# 03_-_ESP32.net
KiCad netlist of a schematic drawn in Altium Designer
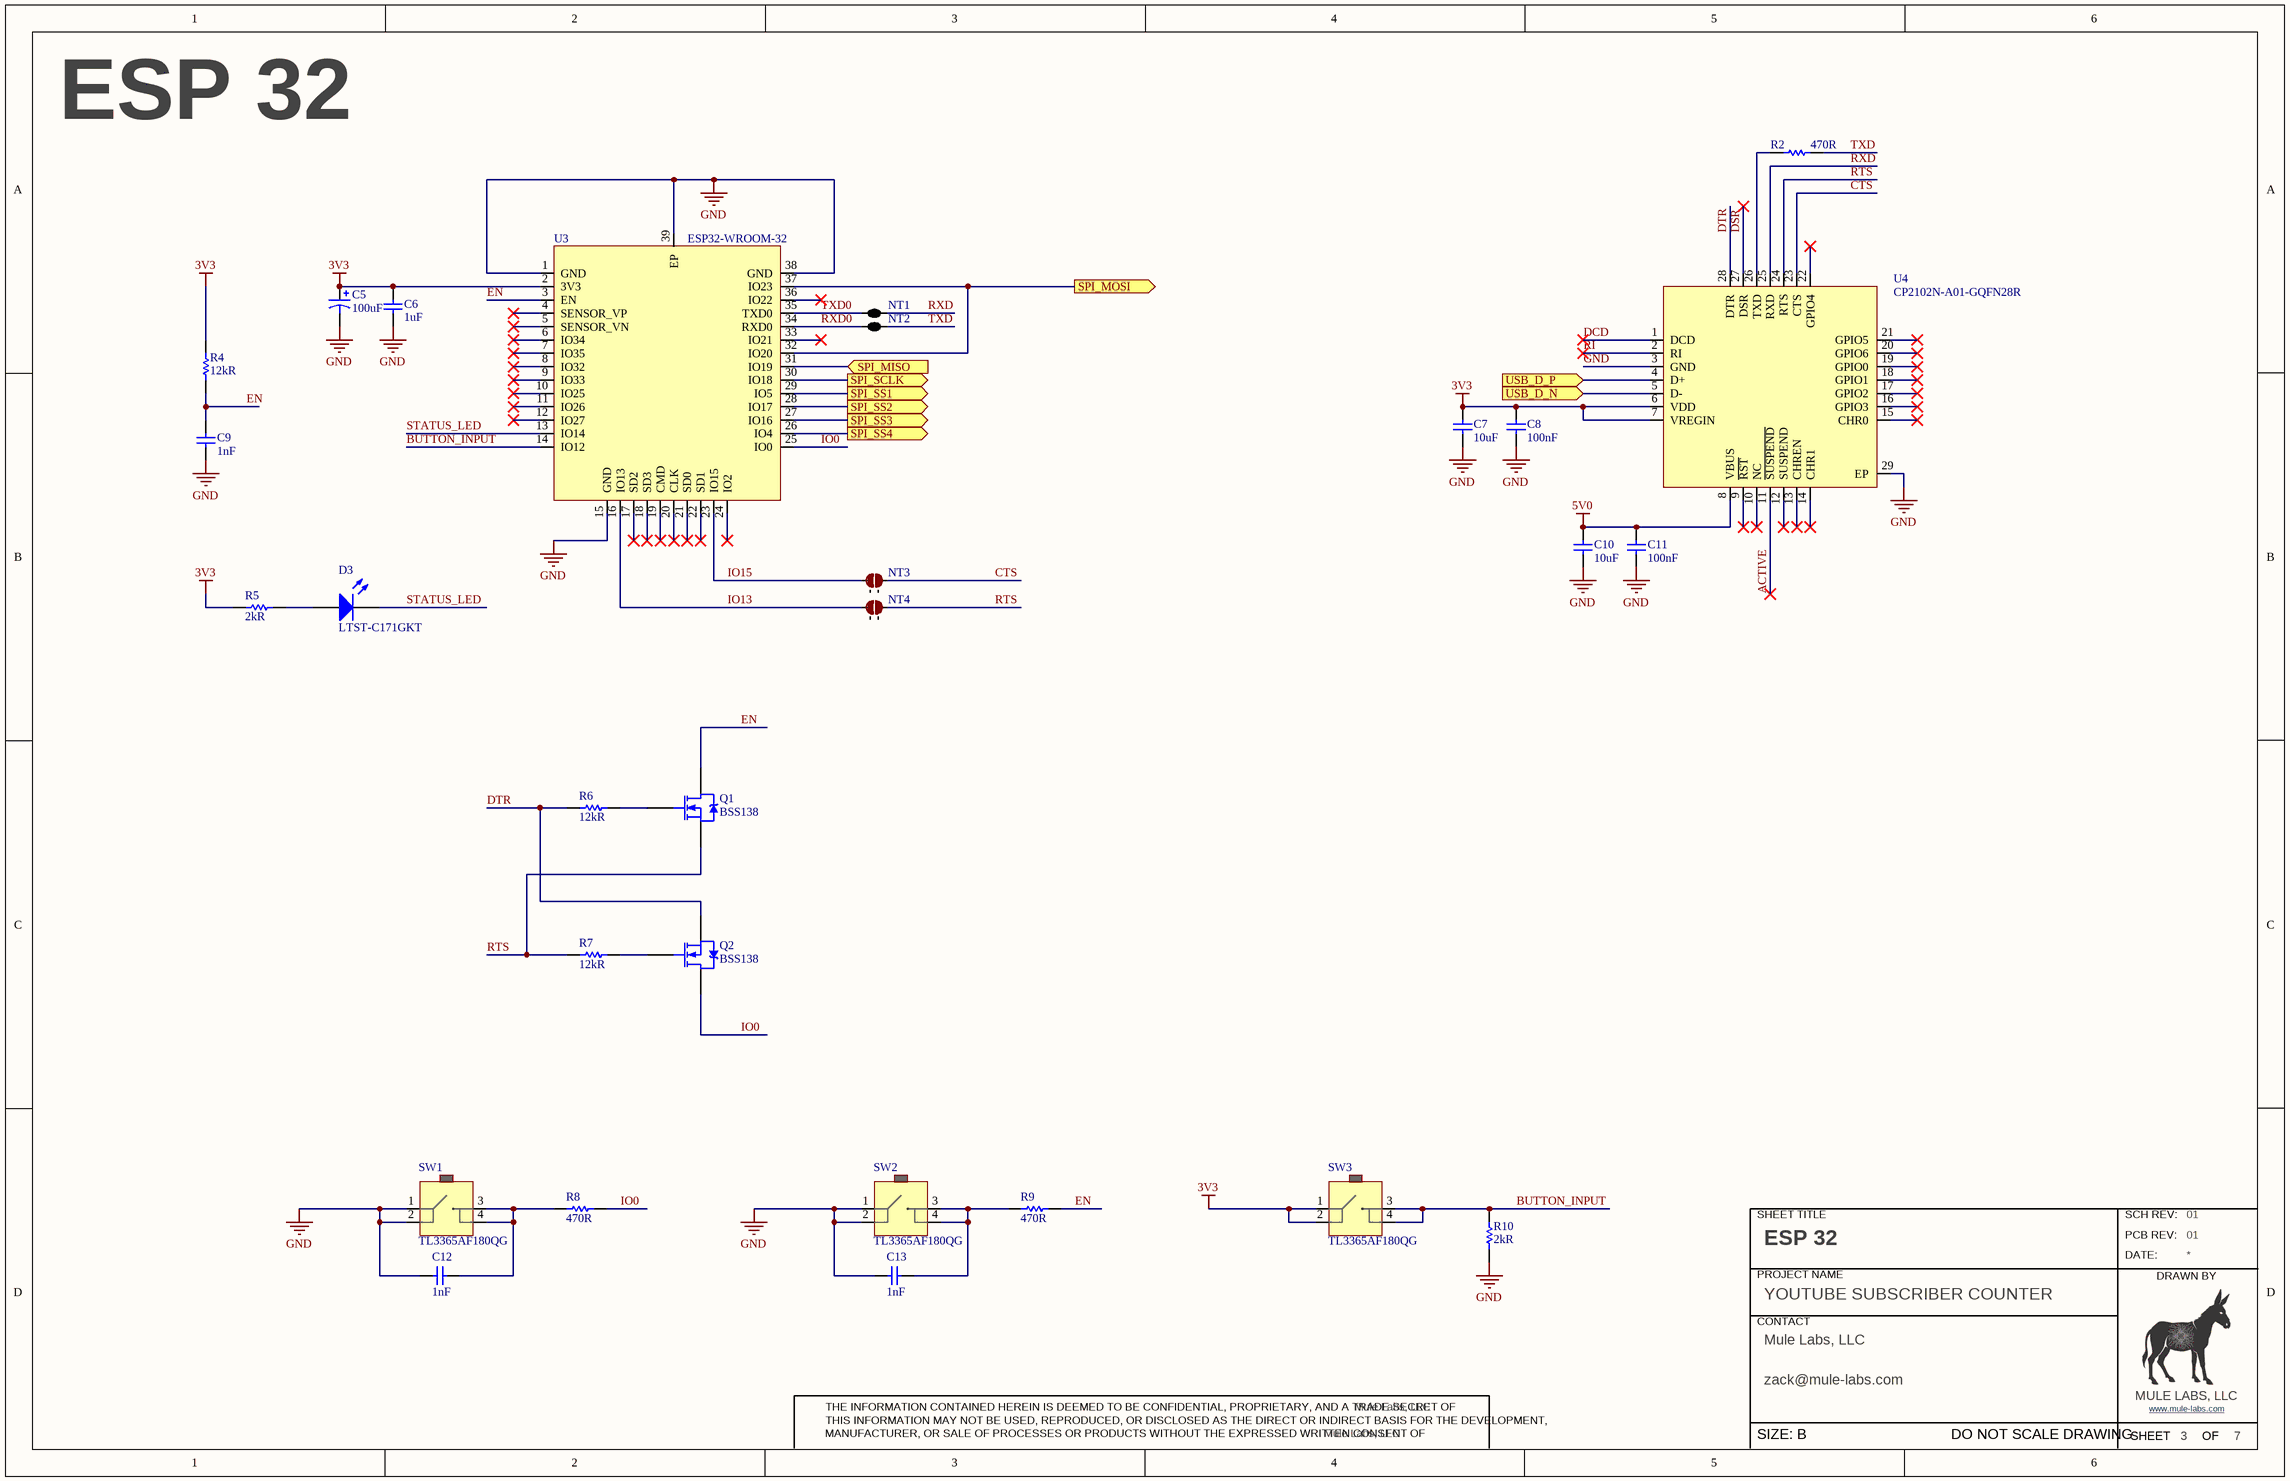
[diagram p0: [03] - ESP32.SchDoc]

(export (version "E")
  (design (tool "Eeschema 10.0.6"))
  (components
    (comp (ref "C5")
      (value "100uF")
      (footprint "INCH 0603 - METRIC 1608 - H090")
      (description "CAP TANT 100UF 20% 6.3V 0603")
      (fields
        (field (name "MANUFACTURER") "Kyocera AVX")
        (field (name "MANUFACTURER PART NUMBER") "F980J107MMAAXE")
      )
      (libsource (lib "Capacitors") (part "F980J107MMAAXE"))
    )
    (comp (ref "C6")
      (value "1uF")
      (footprint "INCH 0603 - METRIC 1608 - H090")
      (description "CAP CER 1UF 16V X7R 0603")
      (fields
        (field (name "MANUFACTURER") "Samsung")
        (field (name "MANUFACTURER PART NUMBER") "CL10B105KO8NNNC")
      )
      (libsource (lib "Capacitors") (part "CL10B105KO8NNNC"))
    )
    (comp (ref "C7")
      (value "10uF")
      (footprint "INCH 0603 - METRIC 1608 - H090")
      (description "CAP CER 10UF 10V X5R 0603")
      (fields
        (field (name "MANUFACTURER") "Murata")
        (field (name "MANUFACTURER PART NUMBER") "GRM188R61A106ME69D")
      )
      (libsource (lib "Capacitors") (part "GRM188R61A106ME69D"))
    )
    (comp (ref "C8")
      (value "100nF")
      (footprint "INCH 0603 - METRIC 1608 - H090")
      (description "CAP CER 0.1UF 25V X7R 0603")
      (fields
        (field (name "MANUFACTURER") "TDK")
        (field (name "MANUFACTURER PART NUMBER") "CGA3E2X7R1E104K080AA")
      )
      (libsource (lib "Capacitors") (part "CGA3E2X7R1E104K080AA"))
    )
    (comp (ref "C9")
      (value "1nF")
      (footprint "INCH 0603 - METRIC 1608 - H090")
      (description "CAP CER 1000PF 50V C0G/NP0 0603")
      (fields
        (field (name "MANUFACTURER") "Samsung")
        (field (name "MANUFACTURER PART NUMBER") "CL10C102JB8NNNC")
      )
      (libsource (lib "Capacitors") (part "CL10C102JB8NNNC"))
    )
    (comp (ref "C10")
      (value "10uF")
      (footprint "INCH 0603 - METRIC 1608 - H090")
      (description "CAP CER 10UF 10V X5R 0603")
      (fields
        (field (name "MANUFACTURER") "Murata")
        (field (name "MANUFACTURER PART NUMBER") "GRM188R61A106ME69D")
      )
      (libsource (lib "Capacitors") (part "GRM188R61A106ME69D"))
    )
    (comp (ref "C11")
      (value "100nF")
      (footprint "INCH 0603 - METRIC 1608 - H090")
      (description "CAP CER 0.1UF 25V X7R 0603")
      (fields
        (field (name "MANUFACTURER") "TDK")
        (field (name "MANUFACTURER PART NUMBER") "CGA3E2X7R1E104K080AA")
      )
      (libsource (lib "Capacitors") (part "CGA3E2X7R1E104K080AA"))
    )
    (comp (ref "C12")
      (value "1nF")
      (footprint "INCH 0603 - METRIC 1608 - H090")
      (description "CAP CER 1000PF 50V C0G/NP0 0603")
      (fields
        (field (name "MANUFACTURER") "Samsung")
        (field (name "MANUFACTURER PART NUMBER") "CL10C102JB8NNNC")
      )
      (libsource (lib "Capacitors") (part "CL10C102JB8NNNC"))
    )
    (comp (ref "C13")
      (value "1nF")
      (footprint "INCH 0603 - METRIC 1608 - H090")
      (description "CAP CER 1000PF 50V C0G/NP0 0603")
      (fields
        (field (name "MANUFACTURER") "Samsung")
        (field (name "MANUFACTURER PART NUMBER") "CL10C102JB8NNNC")
      )
      (libsource (lib "Capacitors") (part "CL10C102JB8NNNC"))
    )
    (comp (ref "D3")
      (value "LTST-C171GKT")
      (footprint "LED - 0805 - GREEN")
      (fields (field (name "MANUFACTURER") "Vishay Lite-On"))
      (libsource (lib "LEDs") (part "LTST-C171GKT"))
    )
    (comp (ref "NT1")
      (value "2 way net tie junction")
      (footprint "2way_HP")
      (libsource (lib "Net Ties") (part "2way"))
    )
    (comp (ref "NT2")
      (value "2 way net tie junction")
      (footprint "2way_HP")
      (libsource (lib "Net Ties") (part "2way"))
    )
    (comp (ref "NT3")
      (value "2 way net solder junction - Normally Open")
      (footprint "2waySolder_NO")
      (libsource (lib "Net Ties") (part "2waySolderNO"))
    )
    (comp (ref "NT4")
      (value "2 way net solder junction - Normally Open")
      (footprint "2waySolder_NO")
      (libsource (lib "Net Ties") (part "2waySolderNO"))
    )
    (comp (ref "Q1")
      (value "BSS138")
      (footprint "SOT95P240X120-3")
      (description "MOSFET N-CH 50V 220MA SOT-23")
      (fields (field (name "MANUFACTURER") "ON Semiconductor / Fairchild"))
      (libsource (lib "Transistors - FET") (part "BSS138"))
    )
    (comp (ref "Q2")
      (value "BSS138")
      (footprint "SOT95P240X120-3")
      (description "MOSFET N-CH 50V 220MA SOT-23")
      (fields (field (name "MANUFACTURER") "ON Semiconductor / Fairchild"))
      (libsource (lib "Transistors - FET") (part "BSS138"))
    )
    (comp (ref "R2")
      (value "470R")
      (footprint "INCH 0603 - METRIC 1608 - H055")
      (description "RES SMD 470 OHM 1% 1/10W 0603")
      (fields
        (field (name "MANUFACTURER") "Yageo")
        (field (name "MANUFACTURER PART NUMBER") "RC0603FR-07470RL")
      )
      (libsource (lib "Resistors") (part "RC0603FR-07470RL"))
    )
    (comp (ref "R4")
      (value "12kR")
      (footprint "INCH 0603 - METRIC 1608 - H055")
      (description "RES SMD 12K OHM 1% 1/10W 0603")
      (fields
        (field (name "MANUFACTURER") "Yageo")
        (field (name "MANUFACTURER PART NUMBER") "RC0603FR-0712KL")
      )
      (libsource (lib "Resistors") (part "RC0603FR-0712KL"))
    )
    (comp (ref "R5")
      (value "2kR")
      (footprint "INCH 0603 - METRIC 1608 - H055")
      (description "RES SMD 2K OHM 1% 1/10W 0603")
      (fields
        (field (name "MANUFACTURER") "Yageo")
        (field (name "MANUFACTURER PART NUMBER") "RC0603FR-072KL")
      )
      (libsource (lib "Resistors") (part "RC0603FR-072KL"))
    )
    (comp (ref "R6")
      (value "12kR")
      (footprint "INCH 0603 - METRIC 1608 - H055")
      (description "RES SMD 12K OHM 1% 1/10W 0603")
      (fields
        (field (name "MANUFACTURER") "Yageo")
        (field (name "MANUFACTURER PART NUMBER") "RC0603FR-0712KL")
      )
      (libsource (lib "Resistors") (part "RC0603FR-0712KL"))
    )
    (comp (ref "R7")
      (value "12kR")
      (footprint "INCH 0603 - METRIC 1608 - H055")
      (description "RES SMD 12K OHM 1% 1/10W 0603")
      (fields
        (field (name "MANUFACTURER") "Yageo")
        (field (name "MANUFACTURER PART NUMBER") "RC0603FR-0712KL")
      )
      (libsource (lib "Resistors") (part "RC0603FR-0712KL"))
    )
    (comp (ref "R8")
      (value "470R")
      (footprint "INCH 0603 - METRIC 1608 - H055")
      (description "RES SMD 470 OHM 1% 1/10W 0603")
      (fields
        (field (name "MANUFACTURER") "Yageo")
        (field (name "MANUFACTURER PART NUMBER") "RC0603FR-07470RL")
      )
      (libsource (lib "Resistors") (part "RC0603FR-07470RL"))
    )
    (comp (ref "R9")
      (value "470R")
      (footprint "INCH 0603 - METRIC 1608 - H055")
      (description "RES SMD 470 OHM 1% 1/10W 0603")
      (fields
        (field (name "MANUFACTURER") "Yageo")
        (field (name "MANUFACTURER PART NUMBER") "RC0603FR-07470RL")
      )
      (libsource (lib "Resistors") (part "RC0603FR-07470RL"))
    )
    (comp (ref "R10")
      (value "2kR")
      (footprint "INCH 0603 - METRIC 1608 - H055")
      (description "RES SMD 2K OHM 1% 1/10W 0603")
      (fields
        (field (name "MANUFACTURER") "Yageo")
        (field (name "MANUFACTURER PART NUMBER") "RC0603FR-072KL")
      )
      (libsource (lib "Resistors") (part "RC0603FR-072KL"))
    )
    (comp (ref "SW1")
      (value "TL3365AF180QG")
      (footprint "ESWITCH_TL3365AF180QG")
      (description "SWITCH TACTILE SPST-NO 0.05A 12V")
      (fields (field (name "MANUFACTURER") "E-Switch"))
      (libsource (lib "Switches") (part "TL3365AF180QG"))
    )
    (comp (ref "SW2")
      (value "TL3365AF180QG")
      (footprint "ESWITCH_TL3365AF180QG")
      (description "SWITCH TACTILE SPST-NO 0.05A 12V")
      (fields (field (name "MANUFACTURER") "E-Switch"))
      (libsource (lib "Switches") (part "TL3365AF180QG"))
    )
    (comp (ref "SW3")
      (value "TL3365AF180QG")
      (footprint "ESWITCH_TL3365AF180QG")
      (description "SWITCH TACTILE SPST-NO 0.05A 12V")
      (fields (field (name "MANUFACTURER") "E-Switch"))
      (libsource (lib "Switches") (part "TL3365AF180QG"))
    )
    (comp (ref "U3")
      (value "ESP32-WROOM-32")
      (footprint "ESPRESSIF_ESP32")
      (description "SMD MODULE, ESP32-D0WDQ6, 32MBIT")
      (fields (field (name "MANUFACTURER") "Espressif Systems"))
      (libsource (lib "ICs - Modules") (part "ESP32-WROOM-32"))
    )
    (comp (ref "U4")
      (value "CP2102N-A01-GQFN28R")
      (footprint "QFN29P50_500X500X80L55X24T310")
      (description "IC BRIDGE USB TO UART 28QFN")
      (fields (field (name "MANUFACTURER") "Silicon Labs"))
      (libsource (lib "ICs - Embedded Comms") (part "CP2102N-A01-GQFN28R"))
    )
  )
  (nets
    (net (code "1") (name "/ACTIVE") (class "Default")
      (node (ref "U4") (pin "11") (pinfunction "~{SUSPEND}_11") (pintype "passive+no_connect"))
    )
    (net (code "2") (name "/BUTTON_INPUT") (class "Default")
      (node (ref "R10") (pin "1") (pintype "passive"))
      (node (ref "SW3") (pin "3") (pinfunction "3_3") (pintype "passive"))
      (node (ref "SW3") (pin "4") (pinfunction "4_4") (pintype "passive"))
      (node (ref "U3") (pin "14") (pinfunction "IO12_14") (pintype "passive"))
    )
    (net (code "3") (name "/CTS") (class "Default")
      (node (ref "NT3") (pin "2") (pinfunction "2_2") (pintype "passive"))
      (node (ref "U4") (pin "23") (pinfunction "CTS_23") (pintype "passive"))
    )
    (net (code "4") (name "/DCD") (class "Default")
      (node (ref "U4") (pin "1") (pinfunction "DCD_1") (pintype "passive+no_connect"))
    )
    (net (code "5") (name "/DSR") (class "Default")
      (node (ref "U4") (pin "27") (pinfunction "DSR_27") (pintype "passive+no_connect"))
    )
    (net (code "6") (name "/DTR") (class "Default")
      (node (ref "Q2") (pin "2") (pinfunction "S_2") (pintype "passive"))
      (node (ref "R6") (pin "1") (pintype "passive"))
      (node (ref "U4") (pin "28") (pinfunction "DTR_28") (pintype "passive"))
    )
    (net (code "7") (name "/EN") (class "Default")
      (node (ref "C9") (pin "1") (pintype "passive"))
      (node (ref "Q1") (pin "3") (pinfunction "D_3") (pintype "passive"))
      (node (ref "R4") (pin "2") (pintype "passive"))
      (node (ref "R9") (pin "2") (pintype "passive"))
      (node (ref "U3") (pin "3") (pinfunction "EN_3") (pintype "passive"))
    )
    (net (code "8") (name "/IO0") (class "Default")
      (node (ref "Q2") (pin "3") (pinfunction "D_3") (pintype "passive"))
      (node (ref "R8") (pin "2") (pintype "passive"))
      (node (ref "U3") (pin "25") (pinfunction "IO0_25") (pintype "passive"))
    )
    (net (code "9") (name "/IO13") (class "Default")
      (node (ref "NT4") (pin "1") (pinfunction "1_1") (pintype "passive"))
      (node (ref "U3") (pin "16") (pinfunction "IO13_16") (pintype "passive"))
    )
    (net (code "10") (name "/IO15") (class "Default")
      (node (ref "NT3") (pin "1") (pinfunction "1_1") (pintype "passive"))
      (node (ref "U3") (pin "23") (pinfunction "IO15_23") (pintype "passive"))
    )
    (net (code "11") (name "/RI") (class "Default")
      (node (ref "U4") (pin "2") (pinfunction "RI_2") (pintype "passive+no_connect"))
    )
    (net (code "12") (name "/RTS") (class "Default")
      (node (ref "NT4") (pin "2") (pinfunction "2_2") (pintype "passive"))
      (node (ref "Q1") (pin "2") (pinfunction "S_2") (pintype "passive"))
      (node (ref "R7") (pin "1") (pintype "passive"))
      (node (ref "U4") (pin "24") (pinfunction "RTS_24") (pintype "passive"))
    )
    (net (code "13") (name "/RXD") (class "Default")
      (node (ref "NT1") (pin "2") (pinfunction "2_2") (pintype "passive"))
      (node (ref "U4") (pin "25") (pinfunction "RXD_25") (pintype "passive"))
    )
    (net (code "14") (name "/RXD0") (class "Default")
      (node (ref "NT2") (pin "1") (pinfunction "1_1") (pintype "passive"))
      (node (ref "U3") (pin "34") (pinfunction "RXD0_34") (pintype "passive"))
    )
    (net (code "15") (name "/SPI_MISO") (class "Default")
      (node (ref "U3") (pin "31") (pinfunction "IO19_31") (pintype "passive"))
    )
    (net (code "16") (name "/SPI_MOSI") (class "Default")
      (node (ref "U3") (pin "32") (pinfunction "IO20_32") (pintype "passive"))
      (node (ref "U3") (pin "37") (pinfunction "IO23_37") (pintype "passive"))
    )
    (net (code "17") (name "/SPI_SCLK") (class "Default")
      (node (ref "U3") (pin "30") (pinfunction "IO18_30") (pintype "passive"))
    )
    (net (code "18") (name "/SPI_SS1") (class "Default")
      (node (ref "U3") (pin "29") (pinfunction "IO5_29") (pintype "passive"))
    )
    (net (code "19") (name "/SPI_SS2") (class "Default")
      (node (ref "U3") (pin "28") (pinfunction "IO17_28") (pintype "passive"))
    )
    (net (code "20") (name "/SPI_SS3") (class "Default")
      (node (ref "U3") (pin "27") (pinfunction "IO16_27") (pintype "passive"))
    )
    (net (code "21") (name "/SPI_SS4") (class "Default")
      (node (ref "U3") (pin "26") (pinfunction "IO4_26") (pintype "passive"))
    )
    (net (code "22") (name "/STATUS_LED") (class "Default")
      (node (ref "D3") (pin "C") (pintype "passive"))
      (node (ref "U3") (pin "13") (pinfunction "IO14_13") (pintype "passive"))
    )
    (net (code "23") (name "/TXD") (class "Default")
      (node (ref "NT2") (pin "2") (pinfunction "2_2") (pintype "passive"))
      (node (ref "R2") (pin "2") (pintype "passive"))
    )
    (net (code "24") (name "/TXD0") (class "Default")
      (node (ref "NT1") (pin "1") (pinfunction "1_1") (pintype "passive"))
      (node (ref "U3") (pin "35") (pinfunction "TXD0_35") (pintype "passive"))
    )
    (net (code "25") (name "/USB_D_N") (class "Default")
      (node (ref "U4") (pin "5") (pinfunction "D-_5") (pintype "passive"))
    )
    (net (code "26") (name "/USB_D_P") (class "Default")
      (node (ref "U4") (pin "4") (pinfunction "D+_4") (pintype "passive"))
    )
    (net (code "27") (name "3V3") (class "Default")
      (node (ref "C5") (pin "1") (pinfunction "1_1") (pintype "passive"))
      (node (ref "C6") (pin "1") (pintype "passive"))
      (node (ref "C7") (pin "1") (pintype "passive"))
      (node (ref "C8") (pin "2") (pintype "passive"))
      (node (ref "R4") (pin "1") (pintype "passive"))
      (node (ref "R5") (pin "1") (pintype "passive"))
      (node (ref "SW3") (pin "1") (pinfunction "1_1") (pintype "passive"))
      (node (ref "SW3") (pin "2") (pinfunction "2_2") (pintype "passive"))
      (node (ref "U3") (pin "2") (pinfunction "3V3_2") (pintype "passive"))
      (node (ref "U4") (pin "6") (pinfunction "VDD_6") (pintype "passive"))
      (node (ref "U4") (pin "7") (pinfunction "VREGIN_7") (pintype "passive"))
    )
    (net (code "28") (name "5V0") (class "Default")
      (node (ref "C10") (pin "1") (pintype "passive"))
      (node (ref "C11") (pin "2") (pintype "passive"))
      (node (ref "U4") (pin "8") (pinfunction "VBUS_8") (pintype "passive"))
    )
    (net (code "29") (name "GND") (class "Default")
      (node (ref "C10") (pin "2") (pintype "passive"))
      (node (ref "C11") (pin "1") (pintype "passive"))
      (node (ref "C12") (pin "1") (pintype "passive"))
      (node (ref "C13") (pin "1") (pintype "passive"))
      (node (ref "C5") (pin "2") (pinfunction "2_2") (pintype "passive"))
      (node (ref "C6") (pin "2") (pintype "passive"))
      (node (ref "C7") (pin "2") (pintype "passive"))
      (node (ref "C8") (pin "1") (pintype "passive"))
      (node (ref "C9") (pin "2") (pintype "passive"))
      (node (ref "R10") (pin "2") (pintype "passive"))
      (node (ref "SW1") (pin "1") (pinfunction "1_1") (pintype "passive"))
      (node (ref "SW1") (pin "2") (pinfunction "2_2") (pintype "passive"))
      (node (ref "SW2") (pin "1") (pinfunction "1_1") (pintype "passive"))
      (node (ref "SW2") (pin "2") (pinfunction "2_2") (pintype "passive"))
      (node (ref "U3") (pin "1") (pinfunction "GND_1") (pintype "passive"))
      (node (ref "U3") (pin "15") (pinfunction "GND_15") (pintype "passive"))
      (node (ref "U3") (pin "38") (pinfunction "GND_38") (pintype "passive"))
      (node (ref "U3") (pin "39") (pinfunction "EP_39") (pintype "passive"))
      (node (ref "U4") (pin "29") (pinfunction "EP_29") (pintype "passive"))
      (node (ref "U4") (pin "3") (pinfunction "GND_3") (pintype "passive"))
    )
    (net (code "30") (name "Net-(C12-Pad2)") (class "Default")
      (node (ref "C12") (pin "2") (pintype "passive"))
      (node (ref "R8") (pin "1") (pintype "passive"))
      (node (ref "SW1") (pin "3") (pinfunction "3_3") (pintype "passive"))
      (node (ref "SW1") (pin "4") (pinfunction "4_4") (pintype "passive"))
    )
    (net (code "31") (name "Net-(C13-Pad2)") (class "Default")
      (node (ref "C13") (pin "2") (pintype "passive"))
      (node (ref "R9") (pin "1") (pintype "passive"))
      (node (ref "SW2") (pin "3") (pinfunction "3_3") (pintype "passive"))
      (node (ref "SW2") (pin "4") (pinfunction "4_4") (pintype "passive"))
    )
    (net (code "32") (name "Net-(D3-PadA)") (class "Default")
      (node (ref "D3") (pin "A") (pintype "passive"))
      (node (ref "R5") (pin "2") (pintype "passive"))
    )
    (net (code "33") (name "Net-(Q1-G)") (class "Default")
      (node (ref "Q1") (pin "1") (pinfunction "G_1") (pintype "passive"))
      (node (ref "R6") (pin "2") (pintype "passive"))
    )
    (net (code "34") (name "Net-(Q2-G)") (class "Default")
      (node (ref "Q2") (pin "1") (pinfunction "G_1") (pintype "passive"))
      (node (ref "R7") (pin "2") (pintype "passive"))
    )
    (net (code "35") (name "Net-(U4-TXD)") (class "Default")
      (node (ref "R2") (pin "1") (pintype "passive"))
      (node (ref "U4") (pin "26") (pinfunction "TXD_26") (pintype "passive"))
    )
    (net (code "36") (name "unconnected-(U3-CLK-Pad20)") (class "Default")
      (node (ref "U3") (pin "20") (pinfunction "CLK_20") (pintype "passive+no_connect"))
    )
    (net (code "37") (name "unconnected-(U3-CMD-Pad19)") (class "Default")
      (node (ref "U3") (pin "19") (pinfunction "CMD_19") (pintype "passive+no_connect"))
    )
    (net (code "38") (name "unconnected-(U3-IO2-Pad24)") (class "Default")
      (node (ref "U3") (pin "24") (pinfunction "IO2_24") (pintype "passive+no_connect"))
    )
    (net (code "39") (name "unconnected-(U3-IO21-Pad33)") (class "Default")
      (node (ref "U3") (pin "33") (pinfunction "IO21_33") (pintype "passive+no_connect"))
    )
    (net (code "40") (name "unconnected-(U3-IO22-Pad36)") (class "Default")
      (node (ref "U3") (pin "36") (pinfunction "IO22_36") (pintype "passive+no_connect"))
    )
    (net (code "41") (name "unconnected-(U3-IO25-Pad10)") (class "Default")
      (node (ref "U3") (pin "10") (pinfunction "IO25_10") (pintype "passive+no_connect"))
    )
    (net (code "42") (name "unconnected-(U3-IO26-Pad11)") (class "Default")
      (node (ref "U3") (pin "11") (pinfunction "IO26_11") (pintype "passive+no_connect"))
    )
    (net (code "43") (name "unconnected-(U3-IO27-Pad12)") (class "Default")
      (node (ref "U3") (pin "12") (pinfunction "IO27_12") (pintype "passive+no_connect"))
    )
    (net (code "44") (name "unconnected-(U3-IO32-Pad8)") (class "Default")
      (node (ref "U3") (pin "8") (pinfunction "IO32_8") (pintype "passive+no_connect"))
    )
    (net (code "45") (name "unconnected-(U3-IO33-Pad9)") (class "Default")
      (node (ref "U3") (pin "9") (pinfunction "IO33_9") (pintype "passive+no_connect"))
    )
    (net (code "46") (name "unconnected-(U3-IO34-Pad6)") (class "Default")
      (node (ref "U3") (pin "6") (pinfunction "IO34_6") (pintype "passive+no_connect"))
    )
    (net (code "47") (name "unconnected-(U3-IO35-Pad7)") (class "Default")
      (node (ref "U3") (pin "7") (pinfunction "IO35_7") (pintype "passive+no_connect"))
    )
    (net (code "48") (name "unconnected-(U3-SD0-Pad21)") (class "Default")
      (node (ref "U3") (pin "21") (pinfunction "SD0_21") (pintype "passive+no_connect"))
    )
    (net (code "49") (name "unconnected-(U3-SD1-Pad22)") (class "Default")
      (node (ref "U3") (pin "22") (pinfunction "SD1_22") (pintype "passive+no_connect"))
    )
    (net (code "50") (name "unconnected-(U3-SD2-Pad17)") (class "Default")
      (node (ref "U3") (pin "17") (pinfunction "SD2_17") (pintype "passive+no_connect"))
    )
    (net (code "51") (name "unconnected-(U3-SD3-Pad18)") (class "Default")
      (node (ref "U3") (pin "18") (pinfunction "SD3_18") (pintype "passive+no_connect"))
    )
    (net (code "52") (name "unconnected-(U3-SENSOR_VN-Pad5)") (class "Default")
      (node (ref "U3") (pin "5") (pinfunction "SENSOR_VN_5") (pintype "passive+no_connect"))
    )
    (net (code "53") (name "unconnected-(U3-SENSOR_VP-Pad4)") (class "Default")
      (node (ref "U3") (pin "4") (pinfunction "SENSOR_VP_4") (pintype "passive+no_connect"))
    )
    (net (code "54") (name "unconnected-(U4-CHR0-Pad15)") (class "Default")
      (node (ref "U4") (pin "15") (pinfunction "CHR0_15") (pintype "passive+no_connect"))
    )
    (net (code "55") (name "unconnected-(U4-CHR1-Pad14)") (class "Default")
      (node (ref "U4") (pin "14") (pinfunction "CHR1_14") (pintype "passive+no_connect"))
    )
    (net (code "56") (name "unconnected-(U4-CHREN-Pad13)") (class "Default")
      (node (ref "U4") (pin "13") (pinfunction "CHREN_13") (pintype "passive+no_connect"))
    )
    (net (code "57") (name "unconnected-(U4-GPIO0-Pad19)") (class "Default")
      (node (ref "U4") (pin "19") (pinfunction "GPIO0_19") (pintype "passive+no_connect"))
    )
    (net (code "58") (name "unconnected-(U4-GPIO1-Pad18)") (class "Default")
      (node (ref "U4") (pin "18") (pinfunction "GPIO1_18") (pintype "passive+no_connect"))
    )
    (net (code "59") (name "unconnected-(U4-GPIO2-Pad17)") (class "Default")
      (node (ref "U4") (pin "17") (pinfunction "GPIO2_17") (pintype "passive+no_connect"))
    )
    (net (code "60") (name "unconnected-(U4-GPIO3-Pad16)") (class "Default")
      (node (ref "U4") (pin "16") (pinfunction "GPIO3_16") (pintype "passive+no_connect"))
    )
    (net (code "61") (name "unconnected-(U4-GPIO4-Pad22)") (class "Default")
      (node (ref "U4") (pin "22") (pinfunction "GPIO4_22") (pintype "passive+no_connect"))
    )
    (net (code "62") (name "unconnected-(U4-GPIO5-Pad21)") (class "Default")
      (node (ref "U4") (pin "21") (pinfunction "GPIO5_21") (pintype "passive+no_connect"))
    )
    (net (code "63") (name "unconnected-(U4-GPIO6-Pad20)") (class "Default")
      (node (ref "U4") (pin "20") (pinfunction "GPIO6_20") (pintype "passive+no_connect"))
    )
    (net (code "64") (name "unconnected-(U4-NC-Pad10)") (class "Default")
      (node (ref "U4") (pin "10") (pinfunction "NC_10") (pintype "passive+no_connect"))
    )
    (net (code "65") (name "unconnected-(U4-SUSPEND-Pad12)") (class "Default")
      (node (ref "U4") (pin "12") (pinfunction "SUSPEND_12") (pintype "passive+no_connect"))
    )
    (net (code "66") (name "unconnected-(U4-~{RST}-Pad9)") (class "Default")
      (node (ref "U4") (pin "9") (pinfunction "~{RST}_9") (pintype "passive+no_connect"))
    )
  )
)
